# M7672.net
KiCad netlist of a schematic drawn in EAGLE
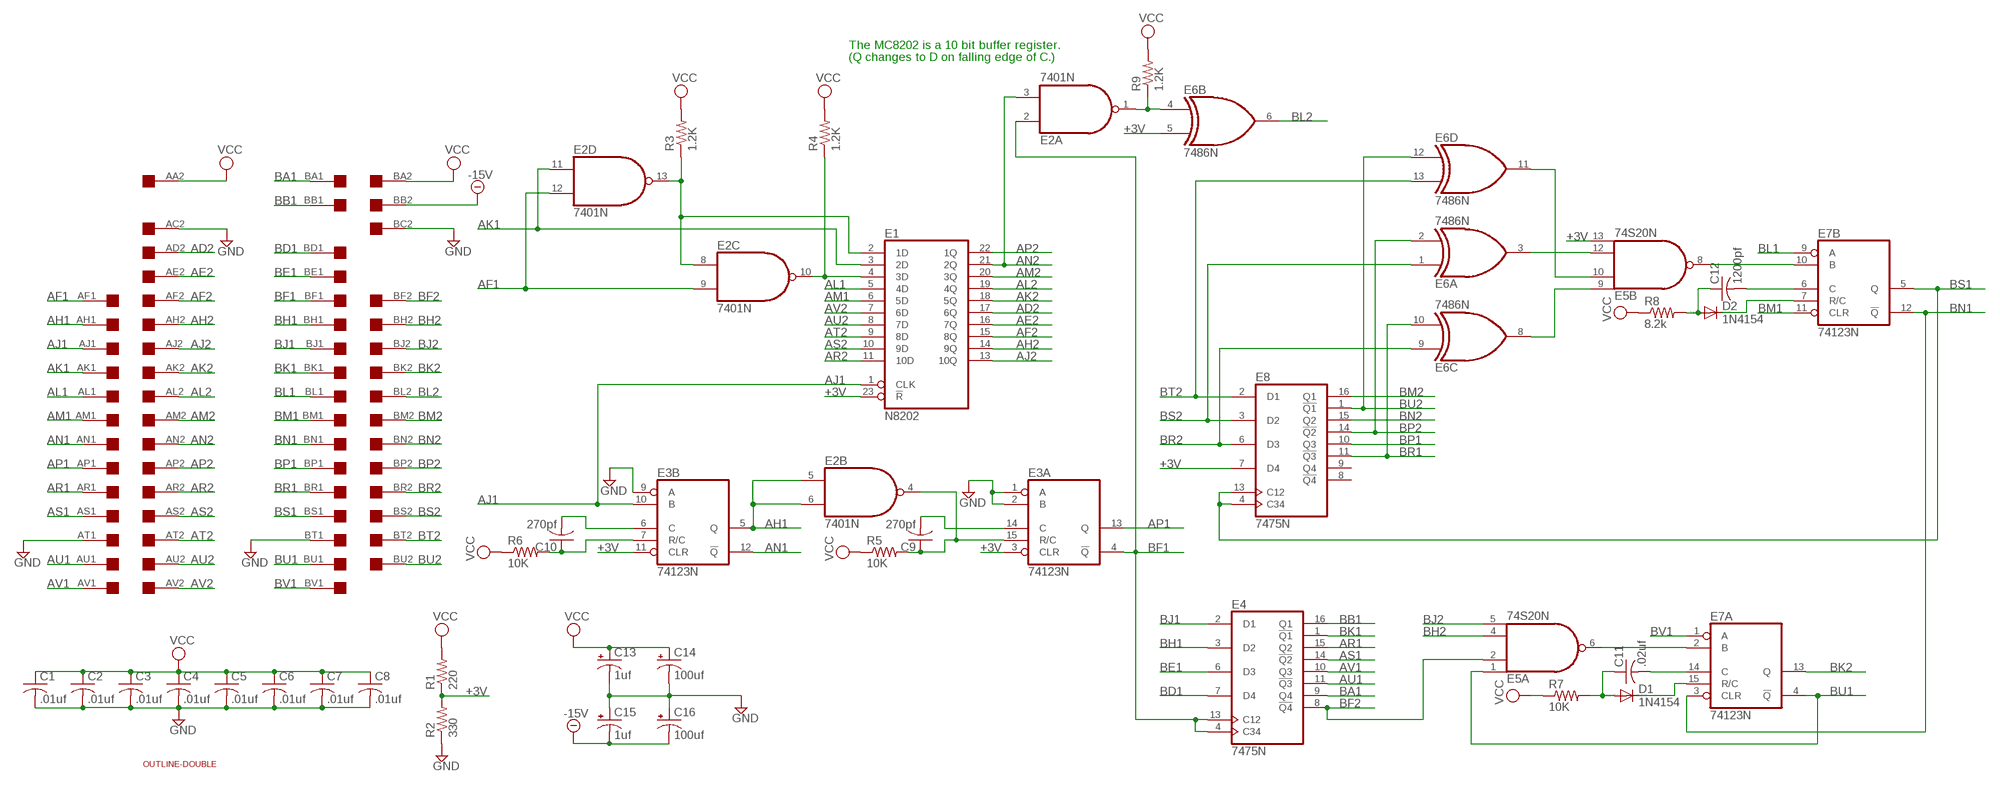
[diagram p0: schematic, sheet 1]

(export (version "E")
  (design (tool "Eeschema 10.0.6"))
  (components
    (comp (ref "C1")
      (value ".01uf")
      (footprint "eagle-import:C050-025X075")
      (libsource (lib "eagle-import") (part "C-US050-025X075"))
    )
    (comp (ref "C2")
      (value ".01uf")
      (footprint "eagle-import:C050-025X075")
      (libsource (lib "eagle-import") (part "C-US050-025X075"))
    )
    (comp (ref "C3")
      (value ".01uf")
      (footprint "eagle-import:C050-025X075")
      (libsource (lib "eagle-import") (part "C-US050-025X075"))
    )
    (comp (ref "C4")
      (value ".01uf")
      (footprint "eagle-import:C050-025X075")
      (libsource (lib "eagle-import") (part "C-US050-025X075"))
    )
    (comp (ref "C5")
      (value ".01uf")
      (footprint "eagle-import:C050-025X075")
      (libsource (lib "eagle-import") (part "C-US050-025X075"))
    )
    (comp (ref "C6")
      (value ".01uf")
      (footprint "eagle-import:C050-025X075")
      (libsource (lib "eagle-import") (part "C-US050-025X075"))
    )
    (comp (ref "C7")
      (value ".01uf")
      (footprint "eagle-import:C050-025X075")
      (libsource (lib "eagle-import") (part "C-US050-025X075"))
    )
    (comp (ref "C8")
      (value ".01uf")
      (footprint "eagle-import:C050-025X075")
      (libsource (lib "eagle-import") (part "C-US050-025X075"))
    )
    (comp (ref "C9")
      (value "270pf")
      (footprint "eagle-import:C050-025X075")
      (libsource (lib "eagle-import") (part "C-US050-025X075"))
    )
    (comp (ref "C10")
      (value "270pf")
      (footprint "eagle-import:C050-025X075")
      (libsource (lib "eagle-import") (part "C-US050-025X075"))
    )
    (comp (ref "C11")
      (value ".02uf")
      (footprint "eagle-import:C050-025X075")
      (libsource (lib "eagle-import") (part "C-US050-025X075"))
    )
    (comp (ref "C12")
      (value "1200pf")
      (footprint "eagle-import:C050-025X075")
      (libsource (lib "eagle-import") (part "C-US050-025X075"))
    )
    (comp (ref "C13")
      (value "1uf")
      (footprint "eagle-import:E30-10")
      (libsource (lib "eagle-import") (part "CPOL-USE30-10AXIAL"))
    )
    (comp (ref "C14")
      (value "100uf")
      (footprint "eagle-import:E30-10")
      (libsource (lib "eagle-import") (part "CPOL-USE30-10AXIAL"))
    )
    (comp (ref "C15")
      (value "1uf")
      (footprint "eagle-import:E30-10")
      (libsource (lib "eagle-import") (part "CPOL-USE30-10AXIAL"))
    )
    (comp (ref "C16")
      (value "100uf")
      (footprint "eagle-import:E30-10")
      (libsource (lib "eagle-import") (part "CPOL-USE30-10AXIAL"))
    )
    (comp (ref "D1")
      (value "1N4154")
      (footprint "eagle-import:DO35-10")
      (libsource (lib "eagle-import") (part "1N4148DO35-10"))
    )
    (comp (ref "D2")
      (value "1N4154")
      (footprint "eagle-import:DO35-10")
      (libsource (lib "eagle-import") (part "1N4148DO35-10"))
    )
    (comp (ref "E1")
      (value "N8202")
      (footprint "eagle-import:DIL24")
      (libsource (lib "eagle-import") (part "N8202"))
    )
    (comp (ref "E2")
      (value "7401N")
      (footprint "eagle-import:DIL14")
      (libsource (lib "eagle-import") (part "7401NLS"))
    )
    (comp (ref "E3")
      (value "74123N")
      (footprint "eagle-import:DIL16")
      (libsource (lib "eagle-import") (part "74123N"))
    )
    (comp (ref "E4")
      (value "7475N")
      (footprint "eagle-import:DIL16")
      (libsource (lib "eagle-import") (part "7475N"))
    )
    (comp (ref "E5")
      (value "74S20N")
      (footprint "eagle-import:DIL14")
      (libsource (lib "eagle-import") (part "7420NS"))
    )
    (comp (ref "E6")
      (value "7486N")
      (footprint "eagle-import:DIL14")
      (libsource (lib "eagle-import") (part "7486N"))
    )
    (comp (ref "E7")
      (value "74123N")
      (footprint "eagle-import:DIL16")
      (libsource (lib "eagle-import") (part "74123N"))
    )
    (comp (ref "E8")
      (value "7475N")
      (footprint "eagle-import:DIL16")
      (libsource (lib "eagle-import") (part "7475N"))
    )
    (comp (ref "EDGE")
      (value "DOUBLE")
      (footprint "eagle-import:EDGE-CON4")
      (libsource (lib "eagle-import") (part "DOUBLE"))
    )
    (comp (ref "R1")
      (value "220")
      (footprint "eagle-import:0207_10")
      (libsource (lib "eagle-import") (part "R-US_0207/10"))
    )
    (comp (ref "R2")
      (value "330")
      (footprint "eagle-import:0207_10")
      (libsource (lib "eagle-import") (part "R-US_0207/10"))
    )
    (comp (ref "R3")
      (value "1.2K")
      (footprint "eagle-import:0207_10")
      (libsource (lib "eagle-import") (part "R-US_0207/10"))
    )
    (comp (ref "R4")
      (value "1.2K")
      (footprint "eagle-import:0207_10")
      (libsource (lib "eagle-import") (part "R-US_0207/10"))
    )
    (comp (ref "R5")
      (value "10K")
      (footprint "eagle-import:0207_10")
      (libsource (lib "eagle-import") (part "R-US_0207/10"))
    )
    (comp (ref "R6")
      (value "10K")
      (footprint "eagle-import:0207_10")
      (libsource (lib "eagle-import") (part "R-US_0207/10"))
    )
    (comp (ref "R7")
      (value "10K")
      (footprint "eagle-import:0207_10")
      (libsource (lib "eagle-import") (part "R-US_0207/10"))
    )
    (comp (ref "R8")
      (value "8.2k")
      (footprint "eagle-import:0207_10")
      (libsource (lib "eagle-import") (part "R-US_0207/10"))
    )
    (comp (ref "R9")
      (value "1.2K")
      (footprint "eagle-import:0207_10")
      (libsource (lib "eagle-import") (part "R-US_0207/10"))
    )
    (comp (ref "U$2")
      (value "OUTLINE-DOUBLE")
      (footprint "eagle-import:DOUBLE")
      (libsource (lib "eagle-import") (part "OUTLINE-DOUBLE"))
    )
  )
  (nets
    (net (code "1") (name "-15V") (class "Default")
      (node (ref "C15") (pin "-") (pinfunction "-_-") (pintype "passive"))
      (node (ref "C16") (pin "-") (pinfunction "-_-") (pintype "passive"))
      (node (ref "EDGE") (pin "BB2") (pinfunction "1_BB2") (pintype "bidirectional"))
    )
    (net (code "2") (name "/+3V") (class "Default")
      (node (ref "E1") (pin "23") (pinfunction "~{R}_23") (pintype "input"))
      (node (ref "E3") (pin "11") (pinfunction "CLR_11") (pintype "input"))
      (node (ref "E3") (pin "3") (pinfunction "CLR_3") (pintype "input"))
      (node (ref "E5") (pin "13") (pinfunction "I3_13") (pintype "input"))
      (node (ref "E6") (pin "5") (pinfunction "I1_5") (pintype "input"))
      (node (ref "E8") (pin "7") (pinfunction "D4_7") (pintype "input"))
      (node (ref "R1") (pin "1") (pinfunction "1_1") (pintype "passive"))
      (node (ref "R2") (pin "2") (pinfunction "2_2") (pintype "passive"))
    )
    (net (code "3") (name "/AD2") (class "Default")
      (node (ref "E1") (pin "17") (pinfunction "6Q_17") (pintype "tri_state"))
      (node (ref "EDGE") (pin "AD2") (pinfunction "1_AD2") (pintype "bidirectional"))
    )
    (net (code "4") (name "/AE2") (class "Default")
      (node (ref "E1") (pin "16") (pinfunction "7Q_16") (pintype "tri_state"))
      (node (ref "EDGE") (pin "AE2") (pinfunction "1_AE2") (pintype "bidirectional"))
    )
    (net (code "5") (name "/AF1") (class "Default")
      (node (ref "E2") (pin "12") (pinfunction "I1_12") (pintype "input"))
      (node (ref "E2") (pin "9") (pinfunction "I1_9") (pintype "input"))
      (node (ref "EDGE") (pin "AF1") (pinfunction "1_AF1") (pintype "bidirectional"))
    )
    (net (code "6") (name "/AF2") (class "Default")
      (node (ref "E1") (pin "15") (pinfunction "8Q_15") (pintype "tri_state"))
      (node (ref "EDGE") (pin "AF2") (pinfunction "1_AF2") (pintype "bidirectional"))
    )
    (net (code "7") (name "/AH1") (class "Default")
      (node (ref "E2") (pin "5") (pinfunction "I0_5") (pintype "input"))
      (node (ref "E2") (pin "6") (pinfunction "I1_6") (pintype "input"))
      (node (ref "E3") (pin "5") (pinfunction "Q_5") (pintype "output"))
      (node (ref "EDGE") (pin "AH1") (pinfunction "1_AH1") (pintype "bidirectional"))
    )
    (net (code "8") (name "/AH2") (class "Default")
      (node (ref "E1") (pin "14") (pinfunction "9Q_14") (pintype "tri_state"))
      (node (ref "EDGE") (pin "AH2") (pinfunction "1_AH2") (pintype "bidirectional"))
    )
    (net (code "9") (name "/AJ1") (class "Default")
      (node (ref "E1") (pin "1") (pinfunction "CLK_1") (pintype "input"))
      (node (ref "E3") (pin "10") (pinfunction "B_10") (pintype "input"))
      (node (ref "EDGE") (pin "AJ1") (pinfunction "1_AJ1") (pintype "bidirectional"))
    )
    (net (code "10") (name "/AJ2") (class "Default")
      (node (ref "E1") (pin "13") (pinfunction "10Q_13") (pintype "tri_state"))
      (node (ref "EDGE") (pin "AJ2") (pinfunction "1_AJ2") (pintype "bidirectional"))
    )
    (net (code "11") (name "/AK1") (class "Default")
      (node (ref "E1") (pin "3") (pinfunction "2D_3") (pintype "input"))
      (node (ref "E2") (pin "11") (pinfunction "I0_11") (pintype "input"))
      (node (ref "EDGE") (pin "AK1") (pinfunction "1_AK1") (pintype "bidirectional"))
    )
    (net (code "12") (name "/AK2") (class "Default")
      (node (ref "E1") (pin "18") (pinfunction "5Q_18") (pintype "tri_state"))
      (node (ref "EDGE") (pin "AK2") (pinfunction "1_AK2") (pintype "bidirectional"))
    )
    (net (code "13") (name "/AL1") (class "Default")
      (node (ref "E1") (pin "5") (pinfunction "4D_5") (pintype "input"))
      (node (ref "EDGE") (pin "AL1") (pinfunction "1_AL1") (pintype "bidirectional"))
    )
    (net (code "14") (name "/AL2") (class "Default")
      (node (ref "E1") (pin "19") (pinfunction "4Q_19") (pintype "tri_state"))
      (node (ref "EDGE") (pin "AL2") (pinfunction "1_AL2") (pintype "bidirectional"))
    )
    (net (code "15") (name "/AM1") (class "Default")
      (node (ref "E1") (pin "6") (pinfunction "5D_6") (pintype "input"))
      (node (ref "EDGE") (pin "AM1") (pinfunction "1_AM1") (pintype "bidirectional"))
    )
    (net (code "16") (name "/AM2") (class "Default")
      (node (ref "E1") (pin "20") (pinfunction "3Q_20") (pintype "tri_state"))
      (node (ref "EDGE") (pin "AM2") (pinfunction "1_AM2") (pintype "bidirectional"))
    )
    (net (code "17") (name "/AN1") (class "Default")
      (node (ref "E3") (pin "12") (pinfunction "~{Q}_12") (pintype "output"))
      (node (ref "EDGE") (pin "AN1") (pinfunction "1_AN1") (pintype "bidirectional"))
    )
    (net (code "18") (name "/AN2") (class "Default")
      (node (ref "E1") (pin "21") (pinfunction "2Q_21") (pintype "tri_state"))
      (node (ref "E2") (pin "3") (pinfunction "I1_3") (pintype "input"))
      (node (ref "EDGE") (pin "AN2") (pinfunction "1_AN2") (pintype "bidirectional"))
    )
    (net (code "19") (name "/AP1") (class "Default")
      (node (ref "E3") (pin "13") (pinfunction "Q_13") (pintype "output"))
      (node (ref "EDGE") (pin "AP1") (pinfunction "1_AP1") (pintype "bidirectional"))
    )
    (net (code "20") (name "/AP2") (class "Default")
      (node (ref "E1") (pin "22") (pinfunction "1Q_22") (pintype "tri_state"))
      (node (ref "EDGE") (pin "AP2") (pinfunction "1_AP2") (pintype "bidirectional"))
    )
    (net (code "21") (name "/AR1") (class "Default")
      (node (ref "E4") (pin "15") (pinfunction "Q2_15") (pintype "output"))
      (node (ref "EDGE") (pin "AR1") (pinfunction "1_AR1") (pintype "bidirectional"))
    )
    (net (code "22") (name "/AR2") (class "Default")
      (node (ref "E1") (pin "11") (pinfunction "10D_11") (pintype "input"))
      (node (ref "EDGE") (pin "AR2") (pinfunction "1_AR2") (pintype "bidirectional"))
    )
    (net (code "23") (name "/AS1") (class "Default")
      (node (ref "E4") (pin "14") (pinfunction "~{Q2}_14") (pintype "output"))
      (node (ref "EDGE") (pin "AS1") (pinfunction "1_AS1") (pintype "bidirectional"))
    )
    (net (code "24") (name "/AS2") (class "Default")
      (node (ref "E1") (pin "10") (pinfunction "9D_10") (pintype "input"))
      (node (ref "EDGE") (pin "AS2") (pinfunction "1_AS2") (pintype "bidirectional"))
    )
    (net (code "25") (name "/AT2") (class "Default")
      (node (ref "E1") (pin "9") (pinfunction "8D_9") (pintype "input"))
      (node (ref "EDGE") (pin "AT2") (pinfunction "1_AT2") (pintype "bidirectional"))
    )
    (net (code "26") (name "/AU1") (class "Default")
      (node (ref "E4") (pin "11") (pinfunction "~{Q3}_11") (pintype "output"))
      (node (ref "EDGE") (pin "AU1") (pinfunction "1_AU1") (pintype "bidirectional"))
    )
    (net (code "27") (name "/AU2") (class "Default")
      (node (ref "E1") (pin "8") (pinfunction "7D_8") (pintype "input"))
      (node (ref "EDGE") (pin "AU2") (pinfunction "1_AU2") (pintype "bidirectional"))
    )
    (net (code "28") (name "/AV1") (class "Default")
      (node (ref "E4") (pin "10") (pinfunction "Q3_10") (pintype "output"))
      (node (ref "EDGE") (pin "AV1") (pinfunction "1_AV1") (pintype "bidirectional"))
    )
    (net (code "29") (name "/AV2") (class "Default")
      (node (ref "E1") (pin "7") (pinfunction "6D_7") (pintype "input"))
      (node (ref "EDGE") (pin "AV2") (pinfunction "1_AV2") (pintype "bidirectional"))
    )
    (net (code "30") (name "/BA1") (class "Default")
      (node (ref "E4") (pin "9") (pinfunction "Q4_9") (pintype "output"))
      (node (ref "EDGE") (pin "BA1") (pinfunction "1_BA1") (pintype "bidirectional"))
    )
    (net (code "31") (name "/BB1") (class "Default")
      (node (ref "E4") (pin "16") (pinfunction "Q1_16") (pintype "output"))
      (node (ref "EDGE") (pin "BB1") (pinfunction "1_BB1") (pintype "bidirectional"))
    )
    (net (code "32") (name "/BD1") (class "Default")
      (node (ref "E4") (pin "7") (pinfunction "D4_7") (pintype "input"))
      (node (ref "EDGE") (pin "BD1") (pinfunction "1_BD1") (pintype "bidirectional"))
    )
    (net (code "33") (name "/BE1") (class "Default")
      (node (ref "E4") (pin "6") (pinfunction "D3_6") (pintype "input"))
      (node (ref "EDGE") (pin "BE1") (pinfunction "1_BE1") (pintype "bidirectional"))
    )
    (net (code "34") (name "/BF1") (class "Default")
      (node (ref "E2") (pin "2") (pinfunction "I0_2") (pintype "input"))
      (node (ref "E3") (pin "4") (pinfunction "~{Q}_4") (pintype "output"))
      (node (ref "E4") (pin "13") (pinfunction "C12_13") (pintype "input"))
      (node (ref "E4") (pin "4") (pinfunction "C34_4") (pintype "input"))
      (node (ref "EDGE") (pin "BF1") (pinfunction "1_BF1") (pintype "bidirectional"))
    )
    (net (code "35") (name "/BF2") (class "Default")
      (node (ref "E4") (pin "8") (pinfunction "~{Q4}_8") (pintype "output"))
      (node (ref "E5") (pin "2") (pinfunction "I1_2") (pintype "input"))
      (node (ref "EDGE") (pin "BF2") (pinfunction "1_BF2") (pintype "bidirectional"))
    )
    (net (code "36") (name "/BH1") (class "Default")
      (node (ref "E4") (pin "3") (pinfunction "D2_3") (pintype "input"))
      (node (ref "EDGE") (pin "BH1") (pinfunction "1_BH1") (pintype "bidirectional"))
    )
    (net (code "37") (name "/BH2") (class "Default")
      (node (ref "E5") (pin "4") (pinfunction "I2_4") (pintype "input"))
      (node (ref "EDGE") (pin "BH2") (pinfunction "1_BH2") (pintype "bidirectional"))
    )
    (net (code "38") (name "/BJ1") (class "Default")
      (node (ref "E4") (pin "2") (pinfunction "D1_2") (pintype "input"))
      (node (ref "EDGE") (pin "BJ1") (pinfunction "1_BJ1") (pintype "bidirectional"))
    )
    (net (code "39") (name "/BJ2") (class "Default")
      (node (ref "E5") (pin "5") (pinfunction "I3_5") (pintype "input"))
      (node (ref "EDGE") (pin "BJ2") (pinfunction "1_BJ2") (pintype "bidirectional"))
    )
    (net (code "40") (name "/BK1") (class "Default")
      (node (ref "E4") (pin "1") (pinfunction "~{Q1}_1") (pintype "output"))
      (node (ref "EDGE") (pin "BK1") (pinfunction "1_BK1") (pintype "bidirectional"))
    )
    (net (code "41") (name "/BK2") (class "Default")
      (node (ref "E7") (pin "13") (pinfunction "Q_13") (pintype "output"))
      (node (ref "EDGE") (pin "BK2") (pinfunction "1_BK2") (pintype "bidirectional"))
    )
    (net (code "42") (name "/BL1") (class "Default")
      (node (ref "E7") (pin "9") (pinfunction "A_9") (pintype "input"))
      (node (ref "EDGE") (pin "BL1") (pinfunction "1_BL1") (pintype "bidirectional"))
    )
    (net (code "43") (name "/BL2") (class "Default")
      (node (ref "E6") (pin "6") (pinfunction "O_6") (pintype "output"))
      (node (ref "EDGE") (pin "BL2") (pinfunction "1_BL2") (pintype "bidirectional"))
    )
    (net (code "44") (name "/BM1") (class "Default")
      (node (ref "E7") (pin "11") (pinfunction "CLR_11") (pintype "input"))
      (node (ref "EDGE") (pin "BM1") (pinfunction "1_BM1") (pintype "bidirectional"))
    )
    (net (code "45") (name "/BM2") (class "Default")
      (node (ref "E8") (pin "16") (pinfunction "Q1_16") (pintype "output"))
      (node (ref "EDGE") (pin "BM2") (pinfunction "1_BM2") (pintype "bidirectional"))
    )
    (net (code "46") (name "/BN1") (class "Default")
      (node (ref "E7") (pin "12") (pinfunction "~{Q}_12") (pintype "output"))
      (node (ref "E7") (pin "3") (pinfunction "CLR_3") (pintype "input"))
      (node (ref "EDGE") (pin "BN1") (pinfunction "1_BN1") (pintype "bidirectional"))
    )
    (net (code "47") (name "/BN2") (class "Default")
      (node (ref "E8") (pin "15") (pinfunction "Q2_15") (pintype "output"))
      (node (ref "EDGE") (pin "BN2") (pinfunction "1_BN2") (pintype "bidirectional"))
    )
    (net (code "48") (name "/BP1") (class "Default")
      (node (ref "E8") (pin "10") (pinfunction "Q3_10") (pintype "output"))
      (node (ref "EDGE") (pin "BP1") (pinfunction "1_BP1") (pintype "bidirectional"))
    )
    (net (code "49") (name "/BP2") (class "Default")
      (node (ref "E6") (pin "2") (pinfunction "I1_2") (pintype "input"))
      (node (ref "E8") (pin "14") (pinfunction "~{Q2}_14") (pintype "output"))
      (node (ref "EDGE") (pin "BP2") (pinfunction "1_BP2") (pintype "bidirectional"))
    )
    (net (code "50") (name "/BR1") (class "Default")
      (node (ref "E6") (pin "10") (pinfunction "I1_10") (pintype "input"))
      (node (ref "E8") (pin "11") (pinfunction "~{Q3}_11") (pintype "output"))
      (node (ref "EDGE") (pin "BR1") (pinfunction "1_BR1") (pintype "bidirectional"))
    )
    (net (code "51") (name "/BR2") (class "Default")
      (node (ref "E6") (pin "9") (pinfunction "I0_9") (pintype "input"))
      (node (ref "E8") (pin "6") (pinfunction "D3_6") (pintype "input"))
      (node (ref "EDGE") (pin "BR2") (pinfunction "1_BR2") (pintype "bidirectional"))
    )
    (net (code "52") (name "/BS1") (class "Default")
      (node (ref "E7") (pin "5") (pinfunction "Q_5") (pintype "output"))
      (node (ref "E8") (pin "13") (pinfunction "C12_13") (pintype "input"))
      (node (ref "E8") (pin "4") (pinfunction "C34_4") (pintype "input"))
      (node (ref "EDGE") (pin "BS1") (pinfunction "1_BS1") (pintype "bidirectional"))
    )
    (net (code "53") (name "/BS2") (class "Default")
      (node (ref "E6") (pin "1") (pinfunction "I0_1") (pintype "input"))
      (node (ref "E8") (pin "3") (pinfunction "D2_3") (pintype "input"))
      (node (ref "EDGE") (pin "BS2") (pinfunction "1_BS2") (pintype "bidirectional"))
    )
    (net (code "54") (name "/BT2") (class "Default")
      (node (ref "E6") (pin "13") (pinfunction "I1_13") (pintype "input"))
      (node (ref "E8") (pin "2") (pinfunction "D1_2") (pintype "input"))
      (node (ref "EDGE") (pin "BT2") (pinfunction "1_BT2") (pintype "bidirectional"))
    )
    (net (code "55") (name "/BU1") (class "Default")
      (node (ref "E5") (pin "1") (pinfunction "I0_1") (pintype "input"))
      (node (ref "E7") (pin "4") (pinfunction "~{Q}_4") (pintype "output"))
      (node (ref "EDGE") (pin "BU1") (pinfunction "1_BU1") (pintype "bidirectional"))
    )
    (net (code "56") (name "/BU2") (class "Default")
      (node (ref "E6") (pin "12") (pinfunction "I0_12") (pintype "input"))
      (node (ref "E8") (pin "1") (pinfunction "~{Q1}_1") (pintype "output"))
      (node (ref "EDGE") (pin "BU2") (pinfunction "1_BU2") (pintype "bidirectional"))
    )
    (net (code "57") (name "/BV1") (class "Default")
      (node (ref "E7") (pin "1") (pinfunction "A_1") (pintype "input"))
      (node (ref "EDGE") (pin "BV1") (pinfunction "1_BV1") (pintype "bidirectional"))
    )
    (net (code "58") (name "GND") (class "Default")
      (node (ref "C1") (pin "2") (pinfunction "2_2") (pintype "passive"))
      (node (ref "C13") (pin "-") (pinfunction "-_-") (pintype "passive"))
      (node (ref "C14") (pin "-") (pinfunction "-_-") (pintype "passive"))
      (node (ref "C15") (pin "+") (pinfunction "+_+") (pintype "passive"))
      (node (ref "C16") (pin "+") (pinfunction "+_+") (pintype "passive"))
      (node (ref "C2") (pin "2") (pinfunction "2_2") (pintype "passive"))
      (node (ref "C3") (pin "2") (pinfunction "2_2") (pintype "passive"))
      (node (ref "C4") (pin "2") (pinfunction "2_2") (pintype "passive"))
      (node (ref "C5") (pin "2") (pinfunction "2_2") (pintype "passive"))
      (node (ref "C6") (pin "2") (pinfunction "2_2") (pintype "passive"))
      (node (ref "C7") (pin "2") (pinfunction "2_2") (pintype "passive"))
      (node (ref "C8") (pin "2") (pinfunction "2_2") (pintype "passive"))
      (node (ref "E3") (pin "1") (pinfunction "A_1") (pintype "input"))
      (node (ref "E3") (pin "2") (pinfunction "B_2") (pintype "input"))
      (node (ref "E3") (pin "9") (pinfunction "A_9") (pintype "input"))
      (node (ref "EDGE") (pin "AC2") (pinfunction "1_AC2") (pintype "bidirectional"))
      (node (ref "EDGE") (pin "AT1") (pinfunction "1_AT1") (pintype "bidirectional"))
      (node (ref "EDGE") (pin "BC2") (pinfunction "1_BC2") (pintype "bidirectional"))
      (node (ref "EDGE") (pin "BT1") (pinfunction "1_BT1") (pintype "bidirectional"))
      (node (ref "R2") (pin "1") (pinfunction "1_1") (pintype "passive"))
    )
    (net (code "59") (name "Net-(C11-Pad1)") (class "Default")
      (node (ref "C11") (pin "1") (pinfunction "1_1") (pintype "passive"))
      (node (ref "D1") (pin "A") (pinfunction "A_A") (pintype "passive"))
      (node (ref "R7") (pin "2") (pinfunction "2_2") (pintype "passive"))
    )
    (net (code "60") (name "Net-(C12-Pad1)") (class "Default")
      (node (ref "C12") (pin "1") (pinfunction "1_1") (pintype "passive"))
      (node (ref "D2") (pin "A") (pinfunction "A_A") (pintype "passive"))
      (node (ref "R8") (pin "2") (pinfunction "2_2") (pintype "passive"))
    )
    (net (code "61") (name "Net-(E1A-1D)") (class "Default")
      (node (ref "E1") (pin "2") (pinfunction "1D_2") (pintype "input"))
      (node (ref "E2") (pin "13") (pinfunction "O_13") (pintype "open_collector"))
      (node (ref "E2") (pin "8") (pinfunction "I0_8") (pintype "input"))
      (node (ref "R3") (pin "1") (pinfunction "1_1") (pintype "passive"))
    )
    (net (code "62") (name "Net-(E1A-3D)") (class "Default")
      (node (ref "E1") (pin "4") (pinfunction "3D_4") (pintype "input"))
      (node (ref "E2") (pin "10") (pinfunction "O_10") (pintype "open_collector"))
      (node (ref "R4") (pin "1") (pinfunction "1_1") (pintype "passive"))
    )
    (net (code "63") (name "Net-(E2A-O)") (class "Default")
      (node (ref "E2") (pin "1") (pinfunction "O_1") (pintype "open_collector"))
      (node (ref "E6") (pin "4") (pinfunction "I0_4") (pintype "input"))
      (node (ref "R9") (pin "1") (pinfunction "1_1") (pintype "passive"))
    )
    (net (code "64") (name "Net-(E2B-O)") (class "Default")
      (node (ref "C9") (pin "1") (pinfunction "1_1") (pintype "passive"))
      (node (ref "E2") (pin "4") (pinfunction "O_4") (pintype "open_collector"))
      (node (ref "E3") (pin "15") (pinfunction "R/C_15") (pintype "input"))
      (node (ref "R5") (pin "2") (pinfunction "2_2") (pintype "passive"))
    )
    (net (code "65") (name "Net-(E3A-C)") (class "Default")
      (node (ref "C9") (pin "2") (pinfunction "2_2") (pintype "passive"))
      (node (ref "E3") (pin "14") (pinfunction "C_14") (pintype "input"))
    )
    (net (code "66") (name "Net-(E3B-C)") (class "Default")
      (node (ref "C10") (pin "2") (pinfunction "2_2") (pintype "passive"))
      (node (ref "E3") (pin "6") (pinfunction "C_6") (pintype "input"))
    )
    (net (code "67") (name "Net-(E3B-R{slash}C)") (class "Default")
      (node (ref "C10") (pin "1") (pinfunction "1_1") (pintype "passive"))
      (node (ref "E3") (pin "7") (pinfunction "R/C_7") (pintype "input"))
      (node (ref "R6") (pin "2") (pinfunction "2_2") (pintype "passive"))
    )
    (net (code "68") (name "Net-(E5A-O)") (class "Default")
      (node (ref "E5") (pin "6") (pinfunction "O_6") (pintype "output"))
      (node (ref "E7") (pin "2") (pinfunction "B_2") (pintype "input"))
    )
    (net (code "69") (name "Net-(E5B-I0)") (class "Default")
      (node (ref "E5") (pin "9") (pinfunction "I0_9") (pintype "input"))
      (node (ref "E6") (pin "8") (pinfunction "O_8") (pintype "output"))
    )
    (net (code "70") (name "Net-(E5B-I1)") (class "Default")
      (node (ref "E5") (pin "10") (pinfunction "I1_10") (pintype "input"))
      (node (ref "E6") (pin "11") (pinfunction "O_11") (pintype "output"))
    )
    (net (code "71") (name "Net-(E5B-I2)") (class "Default")
      (node (ref "E5") (pin "12") (pinfunction "I2_12") (pintype "input"))
      (node (ref "E6") (pin "3") (pinfunction "O_3") (pintype "output"))
    )
    (net (code "72") (name "Net-(E5B-O)") (class "Default")
      (node (ref "E5") (pin "8") (pinfunction "O_8") (pintype "output"))
      (node (ref "E7") (pin "10") (pinfunction "B_10") (pintype "input"))
    )
    (net (code "73") (name "Net-(E7A-C)") (class "Default")
      (node (ref "C11") (pin "2") (pinfunction "2_2") (pintype "passive"))
      (node (ref "E7") (pin "14") (pinfunction "C_14") (pintype "input"))
    )
    (net (code "74") (name "Net-(E7A-R{slash}C)") (class "Default")
      (node (ref "D1") (pin "C") (pinfunction "C_C") (pintype "passive"))
      (node (ref "E7") (pin "15") (pinfunction "R/C_15") (pintype "input"))
    )
    (net (code "75") (name "Net-(E7B-C)") (class "Default")
      (node (ref "C12") (pin "2") (pinfunction "2_2") (pintype "passive"))
      (node (ref "E7") (pin "6") (pinfunction "C_6") (pintype "input"))
    )
    (net (code "76") (name "Net-(E7B-R{slash}C)") (class "Default")
      (node (ref "D2") (pin "C") (pinfunction "C_C") (pintype "passive"))
      (node (ref "E7") (pin "7") (pinfunction "R/C_7") (pintype "input"))
    )
    (net (code "77") (name "VCC") (class "Default")
      (node (ref "C1") (pin "1") (pinfunction "1_1") (pintype "passive"))
      (node (ref "C13") (pin "+") (pinfunction "+_+") (pintype "passive"))
      (node (ref "C14") (pin "+") (pinfunction "+_+") (pintype "passive"))
      (node (ref "C2") (pin "1") (pinfunction "1_1") (pintype "passive"))
      (node (ref "C3") (pin "1") (pinfunction "1_1") (pintype "passive"))
      (node (ref "C4") (pin "1") (pinfunction "1_1") (pintype "passive"))
      (node (ref "C5") (pin "1") (pinfunction "1_1") (pintype "passive"))
      (node (ref "C6") (pin "1") (pinfunction "1_1") (pintype "passive"))
      (node (ref "C7") (pin "1") (pinfunction "1_1") (pintype "passive"))
      (node (ref "C8") (pin "1") (pinfunction "1_1") (pintype "passive"))
      (node (ref "EDGE") (pin "AA2") (pinfunction "1_AA2") (pintype "bidirectional"))
      (node (ref "EDGE") (pin "BA2") (pinfunction "1_BA2") (pintype "bidirectional"))
      (node (ref "R1") (pin "2") (pinfunction "2_2") (pintype "passive"))
      (node (ref "R3") (pin "2") (pinfunction "2_2") (pintype "passive"))
      (node (ref "R4") (pin "2") (pinfunction "2_2") (pintype "passive"))
      (node (ref "R5") (pin "1") (pinfunction "1_1") (pintype "passive"))
      (node (ref "R6") (pin "1") (pinfunction "1_1") (pintype "passive"))
      (node (ref "R7") (pin "1") (pinfunction "1_1") (pintype "passive"))
      (node (ref "R8") (pin "1") (pinfunction "1_1") (pintype "passive"))
      (node (ref "R9") (pin "2") (pinfunction "2_2") (pintype "passive"))
    )
    (net (code "78") (name "unconnected-(E8A-Q4-Pad9)") (class "Default")
      (node (ref "E8") (pin "9") (pinfunction "Q4_9") (pintype "output"))
    )
    (net (code "79") (name "unconnected-(E8A-~{Q4}-Pad8)") (class "Default")
      (node (ref "E8") (pin "8") (pinfunction "~{Q4}_8") (pintype "output"))
    )
  )
)
